# W5200_Evaluation_Sheet.net
KiCad netlist of a schematic drawn in Altium Designer
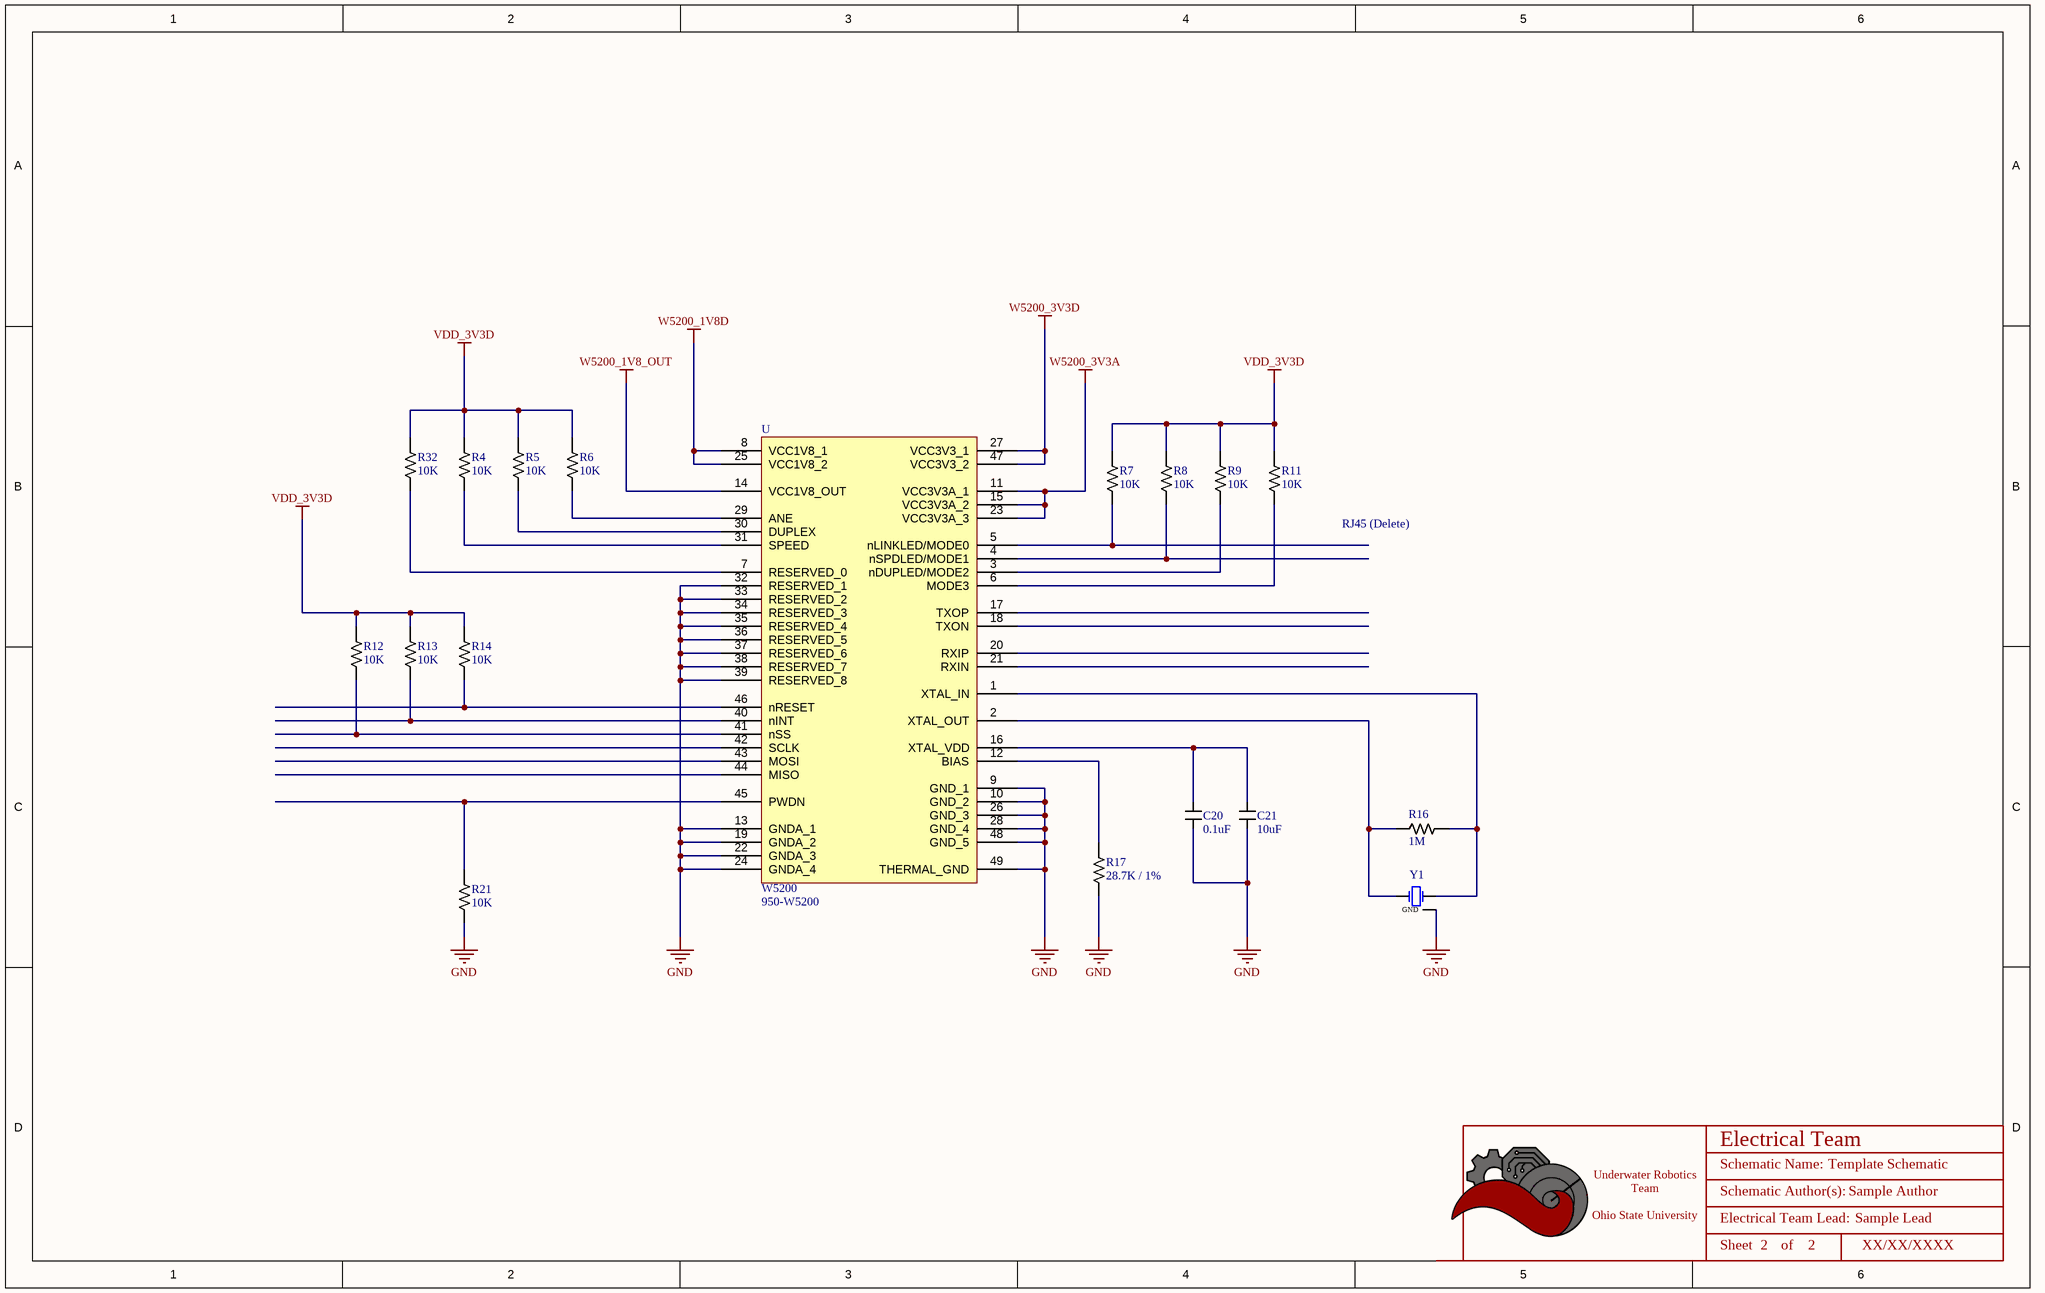
[diagram p0: W5200_Evaluation_Sheet.SchDoc]

(export (version "E")
  (design (tool "Eeschema 10.0.6"))
  (components
    (comp (ref "C20")
      (value "0.1uF")
      (footprint "CAPACITOR_0603")
      (description "Cap 100nF 6.3V +/-10%\r\nCeramic 0603")
      (fields
        (field (name "TOLERANCE") "+/- 10%")
        (field (name "VOLTAGE") "6.3V")
        (field (name "MADE BY") "Flip B")
      )
      (libsource (lib "Capacitors") (part "CAPACITOR_0.1uF_0603"))
    )
    (comp (ref "C21")
      (value "10uF Ceramic 6.3V")
      (footprint "CAPACITOR_0603")
      (description "Cap 10uF 6.3V +/-20%\r\nCeramic 0603")
      (fields
        (field (name "TOLERANCE") "+/- 20%")
        (field (name "VOLTAGE") "6.3V")
        (field (name "VALUE (UF)") "10uF")
        (field (name "MADE BY") "Flip B")
      )
      (libsource (lib "Capacitors") (part "CAPACITOR_10uF_0603"))
    )
    (comp (ref "R4")
      (value "10k Ohm 5% 1/10W")
      (footprint "RESISTOR_0603")
      (description "RES 10k OHM 5% 1/10W 0603")
      (fields
        (field (name "TOLERANCE") "+/- 5%")
        (field (name "VALUE  (OHMS)") "10K")
        (field (name "MADE BY") "Robert Pafford")
      )
      (libsource (lib "Resistors") (part "RESISTOR_10K_0603"))
    )
    (comp (ref "R5")
      (value "10k Ohm 5% 1/10W")
      (footprint "RESISTOR_0603")
      (description "RES 10k OHM 5% 1/10W 0603")
      (fields
        (field (name "TOLERANCE") "+/- 5%")
        (field (name "VALUE  (OHMS)") "10K")
        (field (name "MADE BY") "Robert Pafford")
      )
      (libsource (lib "Resistors") (part "RESISTOR_10K_0603"))
    )
    (comp (ref "R6")
      (value "10k Ohm 5% 1/10W")
      (footprint "RESISTOR_0603")
      (description "RES 10k OHM 5% 1/10W 0603")
      (fields
        (field (name "TOLERANCE") "+/- 5%")
        (field (name "VALUE  (OHMS)") "10K")
        (field (name "MADE BY") "Robert Pafford")
      )
      (libsource (lib "Resistors") (part "RESISTOR_10K_0603"))
    )
    (comp (ref "R7")
      (value "10k Ohm 5% 1/10W")
      (footprint "RESISTOR_0603")
      (description "RES 10k OHM 5% 1/10W 0603")
      (fields
        (field (name "TOLERANCE") "+/- 5%")
        (field (name "VALUE  (OHMS)") "10K")
        (field (name "MADE BY") "Robert Pafford")
      )
      (libsource (lib "Resistors") (part "RESISTOR_10K_0603"))
    )
    (comp (ref "R8")
      (value "10k Ohm 5% 1/10W")
      (footprint "RESISTOR_0603")
      (description "RES 10k OHM 5% 1/10W 0603")
      (fields
        (field (name "TOLERANCE") "+/- 5%")
        (field (name "VALUE  (OHMS)") "10K")
        (field (name "MADE BY") "Robert Pafford")
      )
      (libsource (lib "Resistors") (part "RESISTOR_10K_0603"))
    )
    (comp (ref "R9")
      (value "10k Ohm 5% 1/10W")
      (footprint "RESISTOR_0603")
      (description "RES 10k OHM 5% 1/10W 0603")
      (fields
        (field (name "TOLERANCE") "+/- 5%")
        (field (name "VALUE  (OHMS)") "10K")
        (field (name "MADE BY") "Robert Pafford")
      )
      (libsource (lib "Resistors") (part "RESISTOR_10K_0603"))
    )
    (comp (ref "R11")
      (value "10k Ohm 5% 1/10W")
      (footprint "RESISTOR_0603")
      (description "RES 10k OHM 5% 1/10W 0603")
      (fields
        (field (name "TOLERANCE") "+/- 5%")
        (field (name "VALUE  (OHMS)") "10K")
        (field (name "MADE BY") "Robert Pafford")
      )
      (libsource (lib "Resistors") (part "RESISTOR_10K_0603"))
    )
    (comp (ref "R12")
      (value "10k Ohm 5% 1/10W")
      (footprint "RESISTOR_0603")
      (description "RES 10k OHM 5% 1/10W 0603")
      (fields
        (field (name "TOLERANCE") "+/- 5%")
        (field (name "VALUE  (OHMS)") "10K")
        (field (name "MADE BY") "Robert Pafford")
      )
      (libsource (lib "Resistors") (part "RESISTOR_10K_0603"))
    )
    (comp (ref "R13")
      (value "10k Ohm 5% 1/10W")
      (footprint "RESISTOR_0603")
      (description "RES 10k OHM 5% 1/10W 0603")
      (fields
        (field (name "TOLERANCE") "+/- 5%")
        (field (name "VALUE  (OHMS)") "10K")
        (field (name "MADE BY") "Robert Pafford")
      )
      (libsource (lib "Resistors") (part "RESISTOR_10K_0603"))
    )
    (comp (ref "R14")
      (value "10k Ohm 5% 1/10W")
      (footprint "RESISTOR_0603")
      (description "RES 10k OHM 5% 1/10W 0603")
      (fields
        (field (name "TOLERANCE") "+/- 5%")
        (field (name "VALUE  (OHMS)") "10K")
        (field (name "MADE BY") "Robert Pafford")
      )
      (libsource (lib "Resistors") (part "RESISTOR_10K_0603"))
    )
    (comp (ref "R16")
      (value "1M")
      (footprint "RESISTOR_0603")
      (description "RES 1M OHM 1/8W 0603")
      (fields
        (field (name "TOLERANCE") "+/- 5%")
        (field (name "VALUE  (OHMS)") "1M")
        (field (name "MADE BY") "Robert Pafford")
      )
      (libsource (lib "Resistors") (part "RESISTOR_1M_0603_1"))
    )
    (comp (ref "R17")
      (value "K / 1%")
      (footprint "RESISTOR_0603")
      (description "RES 28.7K OHM 1% 1/8W 0603")
      (fields
        (field (name "TOLERANCE") "+/- 5%")
        (field (name "VALUE  (OHMS)") "28.7K / 1%")
        (field (name "MADE BY") "Robert Pafford")
      )
      (libsource (lib "Resistors") (part "RESISTOR_28.7K / 1%_0603_1"))
    )
    (comp (ref "R21")
      (value "10k Ohm 5% 1/10W")
      (footprint "RESISTOR_0603")
      (description "RES 10k OHM 5% 1/10W 0603")
      (fields
        (field (name "TOLERANCE") "+/- 5%")
        (field (name "VALUE  (OHMS)") "10K")
        (field (name "MADE BY") "Robert Pafford")
      )
      (libsource (lib "Resistors") (part "RESISTOR_10K_0603"))
    )
    (comp (ref "R32")
      (value "10k Ohm 5% 1/10W")
      (footprint "RESISTOR_0603")
      (description "RES 10k OHM 5% 1/10W 0603")
      (fields
        (field (name "TOLERANCE") "+/- 5%")
        (field (name "VALUE  (OHMS)") "10K")
        (field (name "MADE BY") "Robert Pafford")
      )
      (libsource (lib "Resistors") (part "RESISTOR_10K_0603"))
    )
    (comp (ref "U")
      (value "W5200")
      (footprint "QFN-48")
      (description "WIZNET W5200\r\n48QFN (7x7 mm)")
      (fields
        (field (name "MF") "Texas Instruments")
        (field (name "MP") "LM1117IMPX-3.3/NOPB")
        (field (name "SUPPLIER PART NUMBER 1") "950-W5200")
        (field (name "CREATED BY:") "Siddharth.V")
      )
      (libsource (lib "Integrated Circuits") (part "W5200"))
    )
    (comp (ref "Y1")
      (value "CRYSTAL 12.0000MHZ 18PF SMD")
      (footprint "4-SMD No Lead Crystal")
      (description "25 MHz ±20ppm Crystal 18pF")
      (fields (field (name "MADE BY") "Robert Pafford"))
      (libsource (lib "Crystals") (part "CRYSTAL_25MHz_SMD_1"))
    )
  )
  (nets
    (net (code "1") (name "GND") (class "Default")
      (node (ref "C20") (pin "2") (pinfunction "2_2") (pintype "passive"))
      (node (ref "C21") (pin "2") (pinfunction "2_2") (pintype "passive"))
      (node (ref "R17") (pin "2") (pinfunction "2_2") (pintype "passive"))
      (node (ref "R21") (pin "2") (pinfunction "2_2") (pintype "passive"))
      (node (ref "U") (pin "10") (pinfunction "GND_2_10") (pintype "passive"))
      (node (ref "U") (pin "13") (pinfunction "GNDA_1_13") (pintype "passive"))
      (node (ref "U") (pin "19") (pinfunction "GNDA_2_19") (pintype "passive"))
      (node (ref "U") (pin "22") (pinfunction "GNDA_3_22") (pintype "passive"))
      (node (ref "U") (pin "24") (pinfunction "GNDA_4_24") (pintype "passive"))
      (node (ref "U") (pin "26") (pinfunction "GND_3_26") (pintype "passive"))
      (node (ref "U") (pin "28") (pinfunction "GND_4_28") (pintype "passive"))
      (node (ref "U") (pin "32") (pinfunction "RESERVED_1_32") (pintype "passive"))
      (node (ref "U") (pin "33") (pinfunction "RESERVED_2_33") (pintype "passive"))
      (node (ref "U") (pin "34") (pinfunction "RESERVED_3_34") (pintype "passive"))
      (node (ref "U") (pin "35") (pinfunction "RESERVED_4_35") (pintype "passive"))
      (node (ref "U") (pin "36") (pinfunction "RESERVED_5_36") (pintype "passive"))
      (node (ref "U") (pin "37") (pinfunction "RESERVED_6_37") (pintype "passive"))
      (node (ref "U") (pin "38") (pinfunction "RESERVED_7_38") (pintype "passive"))
      (node (ref "U") (pin "39") (pinfunction "RESERVED_8_39") (pintype "passive"))
      (node (ref "U") (pin "48") (pinfunction "GND_5_48") (pintype "passive"))
      (node (ref "U") (pin "49") (pinfunction "THERMAL_GND_49") (pintype "passive"))
      (node (ref "U") (pin "9") (pinfunction "GND_1_9") (pintype "passive"))
      (node (ref "Y1") (pin "GND") (pinfunction "GND_GND") (pintype "power_in"))
    )
    (net (code "2") (name "Net-(U-ANE)") (class "Default")
      (node (ref "R6") (pin "2") (pinfunction "2_2") (pintype "passive"))
      (node (ref "U") (pin "29") (pinfunction "ANE_29") (pintype "passive"))
    )
    (net (code "3") (name "Net-(U-BIAS)") (class "Default")
      (node (ref "R17") (pin "1") (pinfunction "1_1") (pintype "passive"))
      (node (ref "U") (pin "12") (pinfunction "BIAS_12") (pintype "passive"))
    )
    (net (code "4") (name "Net-(U-DUPLEX)") (class "Default")
      (node (ref "R5") (pin "2") (pinfunction "2_2") (pintype "passive"))
      (node (ref "U") (pin "30") (pinfunction "DUPLEX_30") (pintype "passive"))
    )
    (net (code "5") (name "Net-(U-MODE3)") (class "Default")
      (node (ref "R11") (pin "2") (pinfunction "2_2") (pintype "passive"))
      (node (ref "U") (pin "6") (pinfunction "MODE3_6") (pintype "passive"))
    )
    (net (code "6") (name "Net-(U-PWDN)") (class "Default")
      (node (ref "R21") (pin "1") (pinfunction "1_1") (pintype "passive"))
      (node (ref "U") (pin "45") (pinfunction "PWDN_45") (pintype "passive"))
    )
    (net (code "7") (name "Net-(U-RESERVED_0)") (class "Default")
      (node (ref "R32") (pin "2") (pinfunction "2_2") (pintype "passive"))
      (node (ref "U") (pin "7") (pinfunction "RESERVED_0_7") (pintype "passive"))
    )
    (net (code "8") (name "Net-(U-SPEED)") (class "Default")
      (node (ref "R4") (pin "2") (pinfunction "2_2") (pintype "passive"))
      (node (ref "U") (pin "31") (pinfunction "SPEED_31") (pintype "passive"))
    )
    (net (code "9") (name "Net-(U-XTAL_IN)") (class "Default")
      (node (ref "R16") (pin "1") (pinfunction "1_1") (pintype "passive"))
      (node (ref "U") (pin "1") (pinfunction "XTAL_IN_1") (pintype "passive"))
      (node (ref "Y1") (pin "2") (pinfunction "2_2") (pintype "passive"))
    )
    (net (code "10") (name "Net-(U-XTAL_OUT)") (class "Default")
      (node (ref "R16") (pin "2") (pinfunction "2_2") (pintype "passive"))
      (node (ref "U") (pin "2") (pinfunction "XTAL_OUT_2") (pintype "passive"))
      (node (ref "Y1") (pin "1") (pinfunction "1_1") (pintype "passive"))
    )
    (net (code "11") (name "Net-(U-XTAL_VDD)") (class "Default")
      (node (ref "C20") (pin "1") (pinfunction "1_1") (pintype "passive"))
      (node (ref "C21") (pin "1") (pinfunction "1_1") (pintype "passive"))
      (node (ref "U") (pin "16") (pinfunction "XTAL_VDD_16") (pintype "passive"))
    )
    (net (code "12") (name "Net-(U-nDUPLED{slash}MODE2)") (class "Default")
      (node (ref "R9") (pin "2") (pinfunction "2_2") (pintype "passive"))
      (node (ref "U") (pin "3") (pinfunction "nDUPLED/MODE2_3") (pintype "passive"))
    )
    (net (code "13") (name "Net-(U-nINT)") (class "Default")
      (node (ref "R13") (pin "2") (pinfunction "2_2") (pintype "passive"))
      (node (ref "U") (pin "40") (pinfunction "nINT_40") (pintype "passive"))
    )
    (net (code "14") (name "Net-(U-nLINKLED{slash}MODE0)") (class "Default")
      (node (ref "R7") (pin "2") (pinfunction "2_2") (pintype "passive"))
      (node (ref "U") (pin "5") (pinfunction "nLINKLED/MODE0_5") (pintype "passive"))
    )
    (net (code "15") (name "Net-(U-nRESET)") (class "Default")
      (node (ref "R14") (pin "2") (pinfunction "2_2") (pintype "passive"))
      (node (ref "U") (pin "46") (pinfunction "nRESET_46") (pintype "passive"))
    )
    (net (code "16") (name "Net-(U-nSPDLED{slash}MODE1)") (class "Default")
      (node (ref "R8") (pin "2") (pinfunction "2_2") (pintype "passive"))
      (node (ref "U") (pin "4") (pinfunction "nSPDLED/MODE1_4") (pintype "passive"))
    )
    (net (code "17") (name "Net-(U-nSS)") (class "Default")
      (node (ref "R12") (pin "2") (pinfunction "2_2") (pintype "passive"))
      (node (ref "U") (pin "41") (pinfunction "nSS_41") (pintype "passive"))
    )
    (net (code "18") (name "VDD_3V3D") (class "Default")
      (node (ref "R11") (pin "1") (pinfunction "1_1") (pintype "passive"))
      (node (ref "R12") (pin "1") (pinfunction "1_1") (pintype "passive"))
      (node (ref "R13") (pin "1") (pinfunction "1_1") (pintype "passive"))
      (node (ref "R14") (pin "1") (pinfunction "1_1") (pintype "passive"))
      (node (ref "R32") (pin "1") (pinfunction "1_1") (pintype "passive"))
      (node (ref "R4") (pin "1") (pinfunction "1_1") (pintype "passive"))
      (node (ref "R5") (pin "1") (pinfunction "1_1") (pintype "passive"))
      (node (ref "R6") (pin "1") (pinfunction "1_1") (pintype "passive"))
      (node (ref "R7") (pin "1") (pinfunction "1_1") (pintype "passive"))
      (node (ref "R8") (pin "1") (pinfunction "1_1") (pintype "passive"))
      (node (ref "R9") (pin "1") (pinfunction "1_1") (pintype "passive"))
    )
    (net (code "19") (name "W5200_1V8D") (class "Default")
      (node (ref "U") (pin "25") (pinfunction "VCC1V8_2_25") (pintype "passive"))
      (node (ref "U") (pin "8") (pinfunction "VCC1V8_1_8") (pintype "passive"))
    )
    (net (code "20") (name "W5200_1V8_OUT") (class "Default")
      (node (ref "U") (pin "14") (pinfunction "VCC1V8_OUT_14") (pintype "passive"))
    )
    (net (code "21") (name "W5200_3V3A") (class "Default")
      (node (ref "U") (pin "11") (pinfunction "VCC3V3A_1_11") (pintype "passive"))
      (node (ref "U") (pin "15") (pinfunction "VCC3V3A_2_15") (pintype "passive"))
      (node (ref "U") (pin "23") (pinfunction "VCC3V3A_3_23") (pintype "passive"))
    )
    (net (code "22") (name "W5200_3V3D") (class "Default")
      (node (ref "U") (pin "27") (pinfunction "VCC3V3_1_27") (pintype "passive"))
      (node (ref "U") (pin "47") (pinfunction "VCC3V3_2_47") (pintype "passive"))
    )
    (net (code "23") (name "unconnected-(U-MISO-Pad44)") (class "Default")
      (node (ref "U") (pin "44") (pinfunction "MISO_44") (pintype "passive"))
    )
    (net (code "24") (name "unconnected-(U-MOSI-Pad43)") (class "Default")
      (node (ref "U") (pin "43") (pinfunction "MOSI_43") (pintype "passive"))
    )
    (net (code "25") (name "unconnected-(U-RXIN-Pad21)") (class "Default")
      (node (ref "U") (pin "21") (pinfunction "RXIN_21") (pintype "passive"))
    )
    (net (code "26") (name "unconnected-(U-RXIP-Pad20)") (class "Default")
      (node (ref "U") (pin "20") (pinfunction "RXIP_20") (pintype "passive"))
    )
    (net (code "27") (name "unconnected-(U-SCLK-Pad42)") (class "Default")
      (node (ref "U") (pin "42") (pinfunction "SCLK_42") (pintype "passive"))
    )
    (net (code "28") (name "unconnected-(U-TXON-Pad18)") (class "Default")
      (node (ref "U") (pin "18") (pinfunction "TXON_18") (pintype "passive"))
    )
    (net (code "29") (name "unconnected-(U-TXOP-Pad17)") (class "Default")
      (node (ref "U") (pin "17") (pinfunction "TXOP_17") (pintype "passive"))
    )
  )
)
